# telemetry-shorter.net
KiCad netlist of a schematic drawn in EAGLE
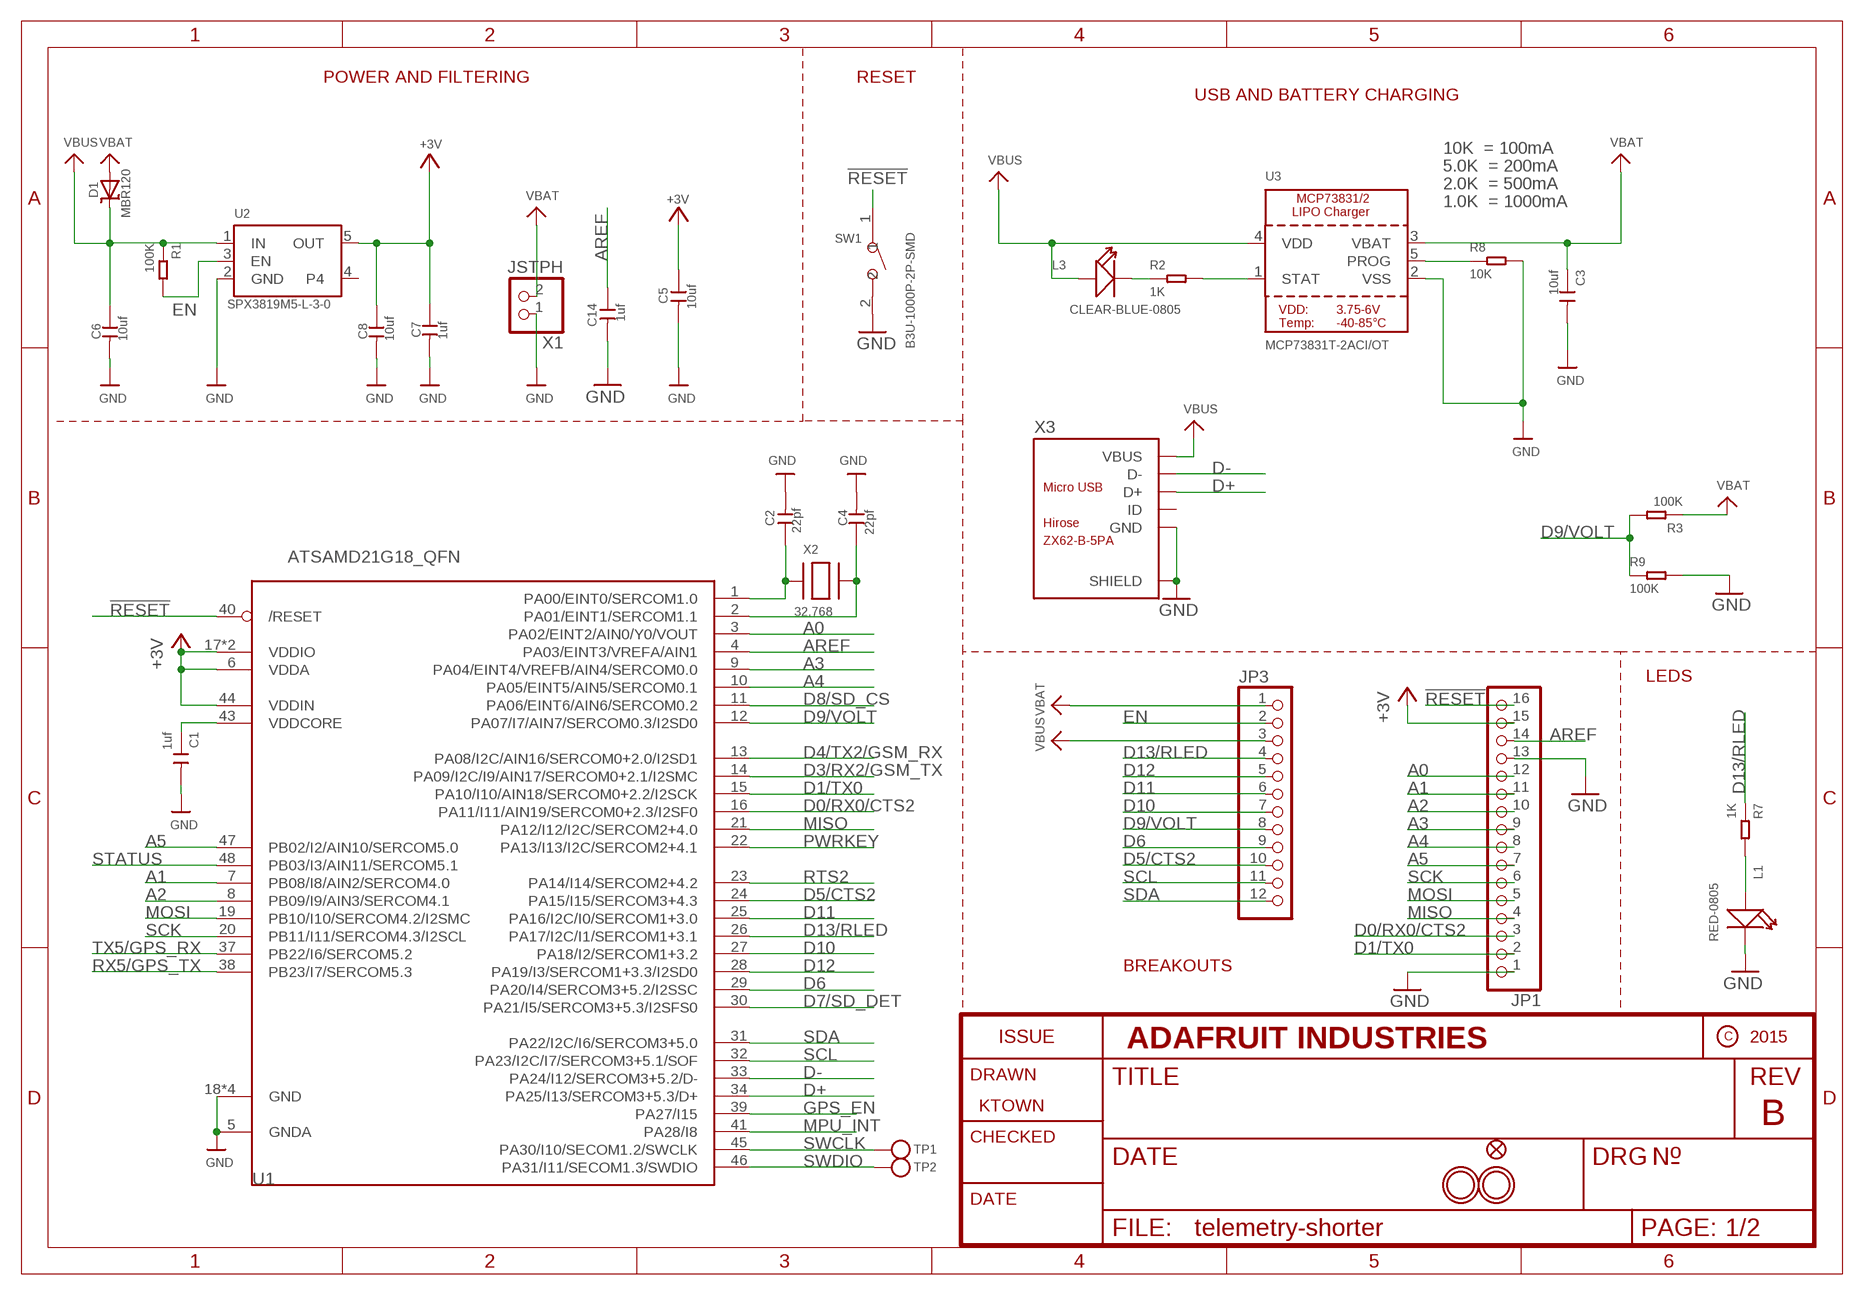
[diagram p0: schematic, sheet 1]
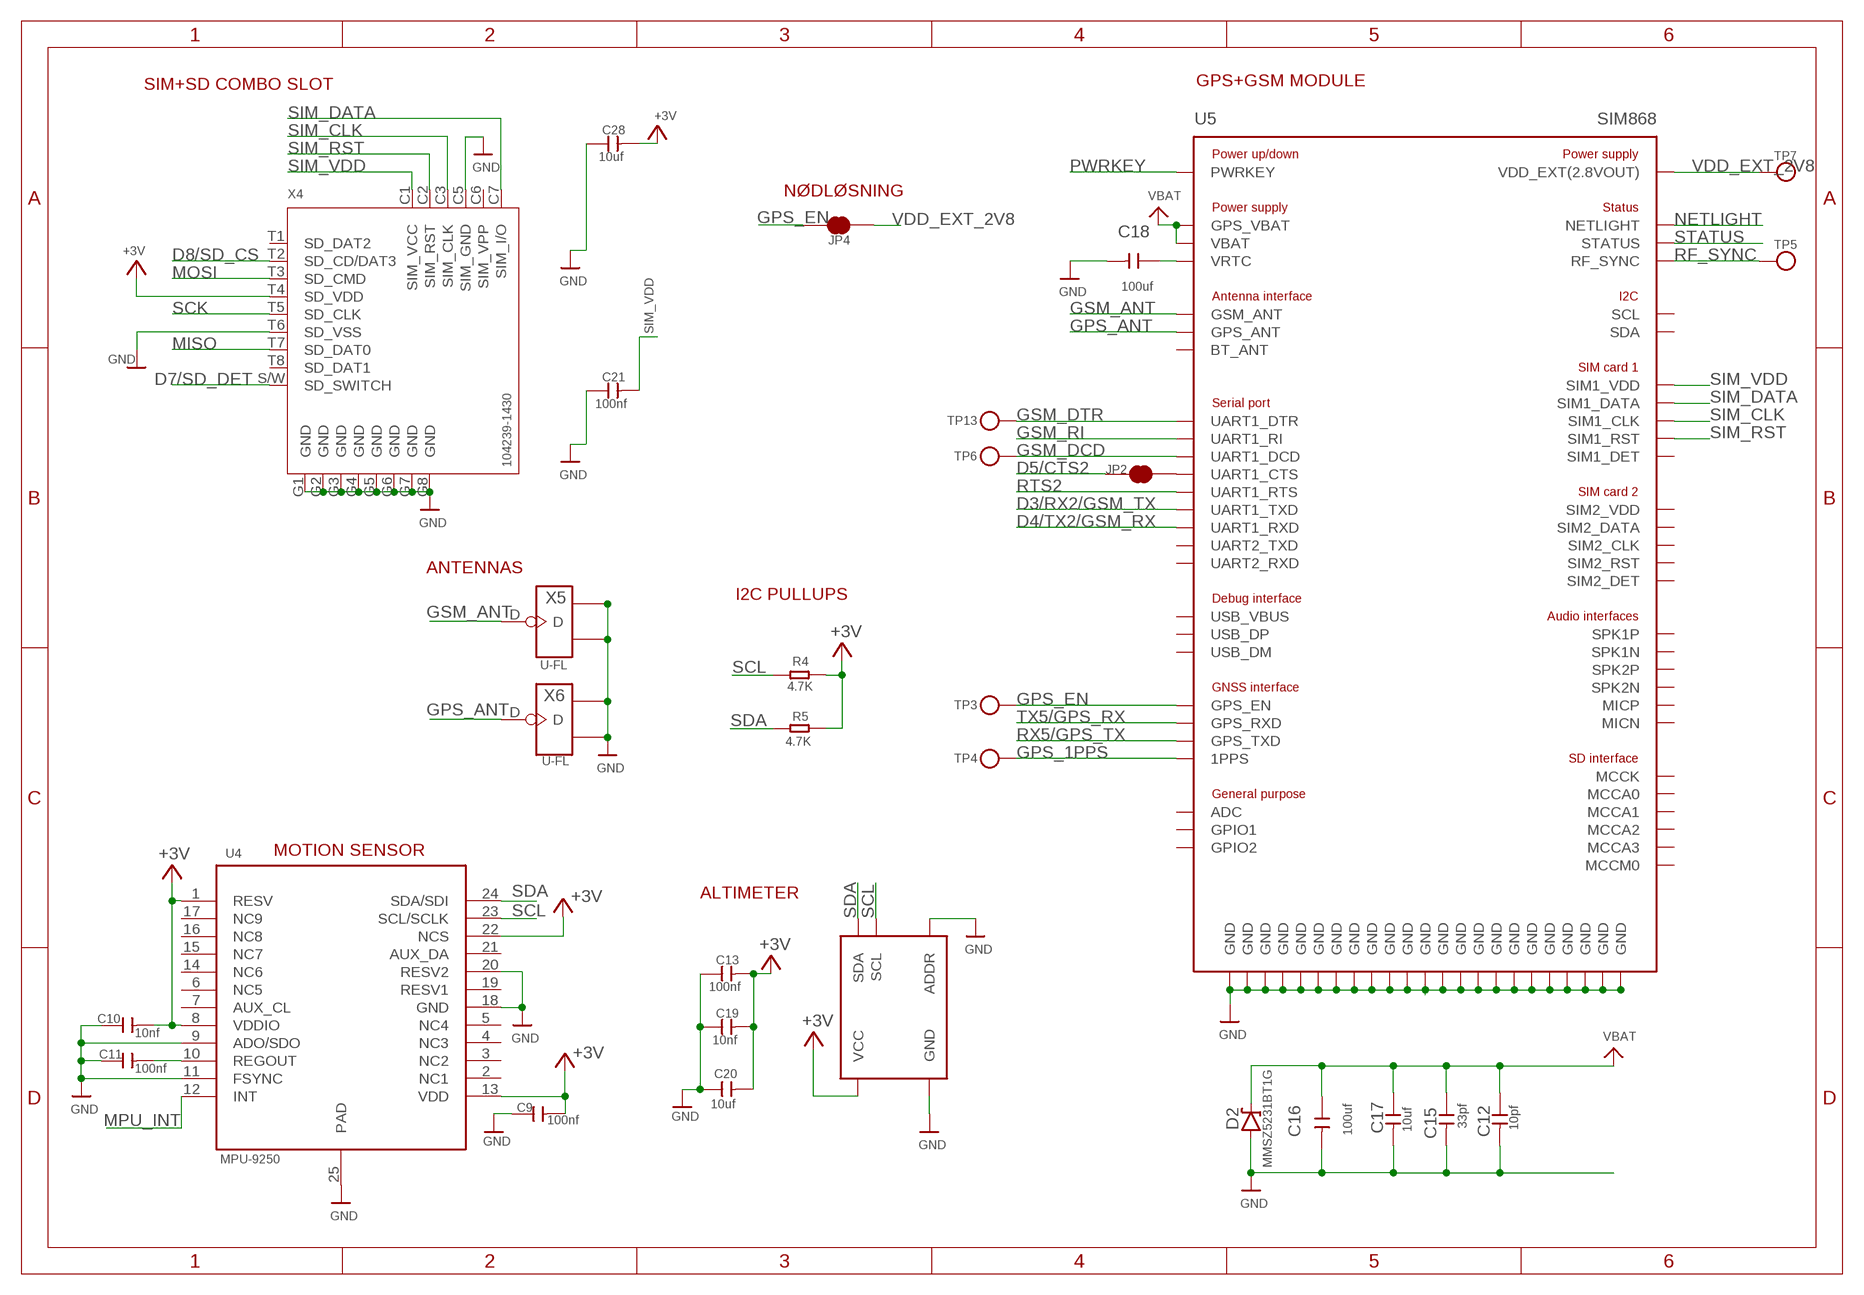
[diagram p1: schematic, sheet 2]

(export (version "E")
  (design (tool "Eeschema 10.0.6"))
  (components
    (comp (ref "C1")
      (value "1uf")
      (footprint "eagle-import:C0603")
      (fields (field (name "MPN") "CC0603KRX7R8BB105"))
      (libsource (lib "eagle-import") (part "CERAMIC-1UF-25V-10%-X7R(0603)"))
    )
    (comp (ref "C2")
      (value "22pf")
      (footprint "eagle-import:C0603")
      (fields (field (name "MPN") "CC0603JRNPO9BN220"))
      (libsource (lib "eagle-import") (part "CERAMIC-22PF-50V-5%-NPO(0603)"))
    )
    (comp (ref "C3")
      (value "10uf")
      (footprint "eagle-import:C0603")
      (fields (field (name "MPN") "CC0603KRX5R6BB106"))
      (libsource (lib "eagle-import") (part "CERAMIC-10UF-10V-10%-X5R(0603)"))
    )
    (comp (ref "C4")
      (value "22pf")
      (footprint "eagle-import:C0603")
      (fields (field (name "MPN") "CC0603JRNPO9BN220"))
      (libsource (lib "eagle-import") (part "CERAMIC-22PF-50V-5%-NPO(0603)"))
    )
    (comp (ref "C5")
      (value "10uf")
      (footprint "eagle-import:C0603")
      (fields (field (name "MPN") "CC0603KRX5R6BB106"))
      (libsource (lib "eagle-import") (part "CERAMIC-10UF-10V-10%-X5R(0603)"))
    )
    (comp (ref "C6")
      (value "10uf")
      (footprint "eagle-import:C0603")
      (fields (field (name "MPN") "CC0603KRX5R6BB106"))
      (libsource (lib "eagle-import") (part "CERAMIC-10UF-10V-10%-X5R(0603)"))
    )
    (comp (ref "C7")
      (value "1uf")
      (footprint "eagle-import:C0603")
      (fields (field (name "MPN") "CC0603KRX7R8BB105"))
      (libsource (lib "eagle-import") (part "CERAMIC-1UF-25V-10%-X7R(0603)"))
    )
    (comp (ref "C8")
      (value "10uf")
      (footprint "eagle-import:C0603")
      (fields (field (name "MPN") "CC0603KRX5R6BB106"))
      (libsource (lib "eagle-import") (part "CERAMIC-10UF-10V-10%-X5R(0603)"))
    )
    (comp (ref "C14")
      (value "1uf")
      (footprint "eagle-import:C0603")
      (fields (field (name "MPN") "CC0603KRX7R8BB105"))
      (libsource (lib "eagle-import") (part "CERAMIC-1UF-25V-10%-X7R(0603)"))
    )
    (comp (ref "D1")
      (value "MBR120")
      (footprint "eagle-import:SOD-123")
      (libsource (lib "eagle-import") (part "DIODE-SCHOTTKYSOD-123"))
    )
    (comp (ref "JP1")
      (value "HEADER-1X16ROUND")
      (footprint "eagle-import:1X16_ROUND")
      (libsource (lib "eagle-import") (part "HEADER-1X16ROUND"))
    )
    (comp (ref "JP3")
      (value "HEADER-1X12")
      (footprint "eagle-import:1X12_ROUND")
      (libsource (lib "eagle-import") (part "HEADER-1X12"))
    )
    (comp (ref "L1")
      (value "RED-0805")
      (footprint "eagle-import:LED-0805")
      (fields (field (name "MPN") "17-215SURC/S530-A2/TR8"))
      (libsource (lib "eagle-import") (part "SMD-LED-CLEAR-RED(0805)"))
    )
    (comp (ref "L3")
      (value "CLEAR-BLUE-0805")
      (footprint "eagle-import:LED-0805")
      (fields (field (name "MPN") "EL-17-215/BHC-AN1P2/3T"))
      (libsource (lib "eagle-import") (part "SMD-LED-CLEAR-BLUE(0805)"))
    )
    (comp (ref "R1")
      (value "100K")
      (footprint "eagle-import:R0603")
      (fields (field (name "MPN") "RC0603JR-07100KL"))
      (libsource (lib "eagle-import") (part "SMD-RES-100K-5%-1/10W(0603)"))
    )
    (comp (ref "R2")
      (value "1K")
      (footprint "eagle-import:R0603")
      (fields (field (name "MPN") "RC0603JR-071KL"))
      (libsource (lib "eagle-import") (part "SMD-RES-1K-5%-1/10W(0603)"))
    )
    (comp (ref "R3")
      (value "100K")
      (footprint "eagle-import:R0603")
      (fields (field (name "MPN") "RC0603FR-07100KL"))
      (libsource (lib "eagle-import") (part "SMD-RES-100K-1%-1/10W(0603)"))
    )
    (comp (ref "R7")
      (value "1K")
      (footprint "eagle-import:R0603")
      (fields (field (name "MPN") "RC0603JR-071KL"))
      (libsource (lib "eagle-import") (part "SMD-RES-1K-5%-1/10W(0603)"))
    )
    (comp (ref "R8")
      (value "10K")
      (footprint "eagle-import:R0603")
      (fields (field (name "MPN") "RC0603JR-0710KL"))
      (libsource (lib "eagle-import") (part "SMD-RES-10K-5%-1/10W(0603)"))
    )
    (comp (ref "R9")
      (value "100K")
      (footprint "eagle-import:R0603")
      (fields (field (name "MPN") "RC0603FR-07100KL"))
      (libsource (lib "eagle-import") (part "SMD-RES-100K-1%-1/10W(0603)"))
    )
    (comp (ref "SW1")
      (value "B3U-1000P-2P-SMD")
      (footprint "eagle-import:SW2-2.6-3.0X2.5X1.2+0.4MM")
      (libsource (lib "eagle-import") (part "SMD-BUTTON(2P-3.0X2.5X1.2+0.4MM)-B3U-1000P-2P-SMD"))
    )
    (comp (ref "TP1")
      (value "TESTPOINTROUND1.5MM")
      (footprint "eagle-import:TESTPOINT_ROUND_1.5MM")
      (libsource (lib "eagle-import") (part "TESTPOINTROUND1.5MM"))
    )
    (comp (ref "TP2")
      (value "TESTPOINTROUND1.5MM")
      (footprint "eagle-import:TESTPOINT_ROUND_1.5MM")
      (libsource (lib "eagle-import") (part "TESTPOINTROUND1.5MM"))
    )
    (comp (ref "U$31")
      (value "MOUNTINGHOLE2.5")
      (footprint "eagle-import:MOUNTINGHOLE_2.5_PLATED")
      (libsource (lib "eagle-import") (part "MOUNTINGHOLE2.5"))
    )
    (comp (ref "U$32")
      (value "MOUNTINGHOLE2.5")
      (footprint "eagle-import:MOUNTINGHOLE_2.5_PLATED")
      (libsource (lib "eagle-import") (part "MOUNTINGHOLE2.5"))
    )
    (comp (ref "U$34")
      (value "FIDUCIAL\"\"")
      (footprint "eagle-import:FIDUCIAL_1MM")
      (libsource (lib "eagle-import") (part "FIDUCIAL{dblquote}{dblquote}"))
    )
    (comp (ref "U1")
      (value "ATSAMD21G18_QFN")
      (footprint "eagle-import:TQFN48_7MM")
      (libsource (lib "eagle-import") (part "ATSAMD21J_QFN"))
    )
    (comp (ref "U2")
      (value "SPX3819M5-L-3-0")
      (footprint "eagle-import:SOT23-5")
      (libsource (lib "eagle-import") (part "VREG_SOT23-5"))
    )
    (comp (ref "U3")
      (value "MCP73831T-2ACI/OT")
      (footprint "eagle-import:SOT23-5")
      (libsource (lib "eagle-import") (part "MCP73831/2"))
    )
    (comp (ref "X1")
      (value "JSTPH")
      (footprint "eagle-import:JSTPH2")
      (libsource (lib "eagle-import") (part "CON_JST_PH_2PIN"))
    )
    (comp (ref "X2")
      (value "32.768")
      (footprint "eagle-import:XTAL3215")
      (libsource (lib "eagle-import") (part "XTAL-3.2X1.5"))
    )
    (comp (ref "X3")
      (value "ZX62-B-5PA")
      (footprint "eagle-import:MICRO-USB5+6P-SMD-0.65-AB")
      (fields (field (name "MFR") "Generic") (field (name "MPN") "AO1SB141B1-067"))
      (libsource (lib "eagle-import") (part "AO1SB141B1-067"))
    )
    (comp (ref "C9")
      (value "100nf")
      (footprint "eagle-import:C0603")
      (fields (field (name "MPN") "CC0603KRX7R9BB104"))
      (libsource (lib "eagle-import") (part "CERAMIC-100NF-50V-10%-X7R(0603)"))
    )
    (comp (ref "C10")
      (value "10nf")
      (footprint "eagle-import:C0603")
      (fields (field (name "MPN") "CC0603KRX7R9BB103"))
      (libsource (lib "eagle-import") (part "CERAMIC-10NF-50V-10%-X7R(0603)"))
    )
    (comp (ref "C11")
      (value "100nf")
      (footprint "eagle-import:C0603")
      (fields (field (name "MPN") "CC0603KRX7R9BB104"))
      (libsource (lib "eagle-import") (part "CERAMIC-100NF-50V-10%-X7R(0603)"))
    )
    (comp (ref "C12")
      (value "10pf")
      (footprint "eagle-import:C0603")
      (fields (field (name "MPN") "CC0603JRNPO9BN100"))
      (libsource (lib "eagle-import") (part "CERAMIC-10PF-50V-5%-NPO(0603)"))
    )
    (comp (ref "C13")
      (value "100nf")
      (footprint "eagle-import:C0603")
      (fields (field (name "MPN") "CC0603KRX7R9BB104"))
      (libsource (lib "eagle-import") (part "CERAMIC-100NF-50V-10%-X7R(0603)"))
    )
    (comp (ref "C15")
      (value "33pf")
      (footprint "eagle-import:C0603")
      (fields (field (name "MPN") "CC0603JRNPO9BN330"))
      (libsource (lib "eagle-import") (part "CERAMIC-33PF-50V-5%-NPO(0603)"))
    )
    (comp (ref "C16")
      (value "100uf")
      (footprint "eagle-import:C1206")
      (fields (field (name "MPN") "GRM31CR60J107ME39L"))
      (libsource (lib "eagle-import") (part "CERAMIC-100UF-6.3V-20%-X5R(1206)"))
    )
    (comp (ref "C17")
      (value "10uf")
      (footprint "eagle-import:C0603")
      (fields (field (name "MPN") "CC0603KRX5R6BB106"))
      (libsource (lib "eagle-import") (part "CERAMIC-10UF-10V-10%-X5R(0603)"))
    )
    (comp (ref "C18")
      (value "100uf")
      (footprint "eagle-import:C1206")
      (fields (field (name "MPN") "GRM31CR60J107ME39L"))
      (libsource (lib "eagle-import") (part "CERAMIC-100UF-6.3V-20%-X5R(1206)"))
    )
    (comp (ref "C19")
      (value "10nf")
      (footprint "eagle-import:C0603")
      (fields (field (name "MPN") "CC0603KRX7R9BB103"))
      (libsource (lib "eagle-import") (part "CERAMIC-10NF-50V-10%-X7R(0603)"))
    )
    (comp (ref "C20")
      (value "10uf")
      (footprint "eagle-import:C0603")
      (fields (field (name "MPN") "CC0603KRX5R6BB106"))
      (libsource (lib "eagle-import") (part "CERAMIC-10UF-10V-10%-X5R(0603)"))
    )
    (comp (ref "C21")
      (value "100nf")
      (footprint "eagle-import:C0603")
      (fields (field (name "MPN") "CC0603KRX7R9BB104"))
      (libsource (lib "eagle-import") (part "CERAMIC-100NF-50V-10%-X7R(0603)"))
    )
    (comp (ref "C28")
      (value "10uf")
      (footprint "eagle-import:C0603")
      (fields (field (name "MPN") "CC0603KRX5R6BB106"))
      (libsource (lib "eagle-import") (part "CERAMIC-10UF-10V-10%-X5R(0603)"))
    )
    (comp (ref "D2")
      (value "MMSZ5231BT1G")
      (footprint "eagle-import:SOD-123")
      (fields (field (name "MFR") "ON SEMICONDUCTOR"))
      (libsource (lib "eagle-import") (part "MMSZ5231BT1G"))
    )
    (comp (ref "JP2")
      (value "JUMPER-PAD-2-NC_BY_TRACE")
      (footprint "eagle-import:PAD-JUMPER-2-NC_BY_TRACE_YES_SILK")
      (libsource (lib "eagle-import") (part "JUMPER-PAD-2-NC_BY_TRACE"))
    )
    (comp (ref "JP4")
      (value "JUMPER-PAD-2-NC_BY_TRACE")
      (footprint "eagle-import:PAD-JUMPER-2-NC_BY_TRACE_YES_SILK")
      (libsource (lib "eagle-import") (part "JUMPER-PAD-2-NC_BY_TRACE"))
    )
    (comp (ref "R4")
      (value "4.7K")
      (footprint "eagle-import:R0603")
      (fields (field (name "MPN") "RC0603JR-074K7L"))
      (libsource (lib "eagle-import") (part "SMD-RES-4.7K-5%-1/10W(0603)"))
    )
    (comp (ref "R5")
      (value "4.7K")
      (footprint "eagle-import:R0603")
      (fields (field (name "MPN") "RC0603JR-074K7L"))
      (libsource (lib "eagle-import") (part "SMD-RES-4.7K-5%-1/10W(0603)"))
    )
    (comp (ref "TP3")
      (value "TESTPOINTROUND1.5MM")
      (footprint "eagle-import:TESTPOINT_ROUND_1.5MM")
      (libsource (lib "eagle-import") (part "TESTPOINTROUND1.5MM"))
    )
    (comp (ref "TP4")
      (value "TESTPOINTROUND1.5MM")
      (footprint "eagle-import:TESTPOINT_ROUND_1.5MM")
      (libsource (lib "eagle-import") (part "TESTPOINTROUND1.5MM"))
    )
    (comp (ref "TP5")
      (value "TESTPOINTROUND1.5MM")
      (footprint "eagle-import:TESTPOINT_ROUND_1.5MM")
      (libsource (lib "eagle-import") (part "TESTPOINTROUND1.5MM"))
    )
    (comp (ref "TP6")
      (value "TESTPOINTROUND1.5MM")
      (footprint "eagle-import:TESTPOINT_ROUND_1.5MM")
      (libsource (lib "eagle-import") (part "TESTPOINTROUND1.5MM"))
    )
    (comp (ref "TP7")
      (value "TESTPOINTROUND1.5MM")
      (footprint "eagle-import:TESTPOINT_ROUND_1.5MM")
      (libsource (lib "eagle-import") (part "TESTPOINTROUND1.5MM"))
    )
    (comp (ref "TP13")
      (value "TESTPOINTROUND1.5MM")
      (footprint "eagle-import:TESTPOINT_ROUND_1.5MM")
      (libsource (lib "eagle-import") (part "TESTPOINTROUND1.5MM"))
    )
    (comp (ref "U4")
      (value "MPU-9250")
      (footprint "eagle-import:LEAD-QFN24")
      (libsource (lib "eagle-import") (part "MPU-9250"))
    )
    (comp (ref "U5")
      (value "SIM868")
      (footprint "eagle-import:SIM868")
      (libsource (lib "eagle-import") (part "SIM868"))
    )
    (comp (ref "U6")
      (value "BMP280")
      (footprint "eagle-import:LGA-8")
      (libsource (lib "eagle-import") (part "BMP280"))
    )
    (comp (ref "X4")
      (value "104239-1430")
      (footprint "eagle-import:MOLEX-SD+SIM-104239")
      (fields (field (name "MPN") "VSHO-21-3301"))
      (libsource (lib "eagle-import") (part "MOLEX-SD+SIM-104239"))
    )
    (comp (ref "X5")
      (value "U-FL")
      (footprint "eagle-import:U-FL3P-SMD-2.6X2.6X1.0MM")
      (libsource (lib "eagle-import") (part "ANTENNA-CONN-U-FL(3P)"))
    )
    (comp (ref "X6")
      (value "U-FL")
      (footprint "eagle-import:U-FL3P-SMD-2.6X2.6X1.0MM")
      (libsource (lib "eagle-import") (part "ANTENNA-CONN-U-FL(3P)"))
    )
  )
  (nets
    (net (code "1") (name "+3V") (class "Default")
      (node (ref "C10") (pin "2") (pinfunction "2_2") (pintype "passive"))
      (node (ref "C13") (pin "2") (pinfunction "2_2") (pintype "passive"))
      (node (ref "C19") (pin "2") (pinfunction "2_2") (pintype "passive"))
      (node (ref "C20") (pin "2") (pinfunction "2_2") (pintype "passive"))
      (node (ref "C28") (pin "2") (pinfunction "2_2") (pintype "passive"))
      (node (ref "C5") (pin "1") (pinfunction "1_1") (pintype "passive"))
      (node (ref "C7") (pin "1") (pinfunction "1_1") (pintype "passive"))
      (node (ref "C8") (pin "1") (pinfunction "1_1") (pintype "passive"))
      (node (ref "C9") (pin "2") (pinfunction "2_2") (pintype "passive"))
      (node (ref "JP1") (pin "15") (pinfunction "15_15") (pintype "passive"))
      (node (ref "R4") (pin "2") (pinfunction "2_2") (pintype "passive"))
      (node (ref "R5") (pin "2") (pinfunction "2_2") (pintype "passive"))
      (node (ref "U1") (pin "17") (pinfunction "VDDIO_17") (pintype "power_in"))
      (node (ref "U1") (pin "36") (pinfunction "VDDIO_36") (pintype "power_in"))
      (node (ref "U1") (pin "44") (pinfunction "VDDIN_44") (pintype "power_in"))
      (node (ref "U1") (pin "6") (pinfunction "VDDA_6") (pintype "power_in"))
      (node (ref "U2") (pin "5") (pinfunction "OUT_5") (pintype "power_in"))
      (node (ref "U4") (pin "1") (pinfunction "RESV_1") (pintype "bidirectional"))
      (node (ref "U4") (pin "13") (pinfunction "VDD_13") (pintype "bidirectional"))
      (node (ref "U4") (pin "22") (pinfunction "NCS_22") (pintype "bidirectional"))
      (node (ref "U4") (pin "8") (pinfunction "VDDIO_8") (pintype "bidirectional"))
      (node (ref "U6") (pin "P2") (pinfunction "VCC_P2") (pintype "bidirectional"))
      (node (ref "U6") (pin "P6") (pinfunction "VCC_P6") (pintype "bidirectional"))
      (node (ref "U6") (pin "P8") (pinfunction "VCC_P8") (pintype "bidirectional"))
      (node (ref "X4") (pin "T4") (pinfunction "SD_VDD_T4") (pintype "bidirectional"))
    )
    (net (code "2") (name "A0") (class "Default")
      (node (ref "JP1") (pin "12") (pinfunction "12_12") (pintype "passive"))
      (node (ref "U1") (pin "3") (pinfunction "PA02/EINT2/AIN0/Y0/VOUT_3") (pintype "bidirectional"))
    )
    (net (code "3") (name "A1") (class "Default")
      (node (ref "JP1") (pin "11") (pinfunction "11_11") (pintype "passive"))
      (node (ref "U1") (pin "7") (pinfunction "PB08/I8/AIN2/SERCOM4.0_7") (pintype "bidirectional"))
    )
    (net (code "4") (name "A2") (class "Default")
      (node (ref "JP1") (pin "10") (pinfunction "10_10") (pintype "passive"))
      (node (ref "U1") (pin "8") (pinfunction "PB09/I9/AIN3/SERCOM4.1_8") (pintype "bidirectional"))
    )
    (net (code "5") (name "A3") (class "Default")
      (node (ref "JP1") (pin "9") (pinfunction "9_9") (pintype "passive"))
      (node (ref "U1") (pin "9") (pinfunction "PA04/EINT4/VREFB/AIN4/SERCOM0.0_9") (pintype "bidirectional"))
    )
    (net (code "6") (name "A4") (class "Default")
      (node (ref "JP1") (pin "8") (pinfunction "8_8") (pintype "passive"))
      (node (ref "U1") (pin "10") (pinfunction "PA05/EINT5/AIN5/SERCOM0.1_10") (pintype "bidirectional"))
    )
    (net (code "7") (name "A5") (class "Default")
      (node (ref "JP1") (pin "7") (pinfunction "7_7") (pintype "passive"))
      (node (ref "U1") (pin "47") (pinfunction "PB02/I2/AIN10/SERCOM5.0_47") (pintype "bidirectional"))
    )
    (net (code "8") (name "AREF") (class "Default")
      (node (ref "C14") (pin "1") (pinfunction "1_1") (pintype "passive"))
      (node (ref "JP1") (pin "14") (pinfunction "14_14") (pintype "passive"))
      (node (ref "U1") (pin "4") (pinfunction "PA03/EINT3/VREFA/AIN1_4") (pintype "bidirectional"))
    )
    (net (code "9") (name "D+") (class "Default")
      (node (ref "U1") (pin "34") (pinfunction "PA25/I13/SERCOM3+5.3/D+_34") (pintype "bidirectional"))
      (node (ref "X3") (pin "3") (pinfunction "D+_3") (pintype "bidirectional"))
    )
    (net (code "10") (name "D-") (class "Default")
      (node (ref "U1") (pin "33") (pinfunction "PA24/I12/SERCOM3+5.2/D-_33") (pintype "bidirectional"))
      (node (ref "X3") (pin "2") (pinfunction "D-_2") (pintype "bidirectional"))
    )
    (net (code "11") (name "D0{slash}RX0{slash}CTS2") (class "Default")
      (node (ref "JP1") (pin "3") (pinfunction "3_3") (pintype "passive"))
      (node (ref "U1") (pin "16") (pinfunction "PA11/I11/AIN19/SERCOM0+2.3/I2SF0_16") (pintype "bidirectional"))
    )
    (net (code "12") (name "D1{slash}TX0") (class "Default")
      (node (ref "JP1") (pin "2") (pinfunction "2_2") (pintype "passive"))
      (node (ref "U1") (pin "15") (pinfunction "PA10/I10/AIN18/SERCOM0+2.2/I2SCK_15") (pintype "bidirectional"))
    )
    (net (code "13") (name "D3{slash}RX2{slash}GSM_TX") (class "Default")
      (node (ref "U1") (pin "14") (pinfunction "PA09/I2C/I9/AIN17/SERCOM0+2.1/I2SMC_14") (pintype "bidirectional"))
      (node (ref "U5") (pin "1_") (pinfunction "UART1_TXD_1_") (pintype "output"))
    )
    (net (code "14") (name "D4{slash}TX2{slash}GSM_RX") (class "Default")
      (node (ref "U1") (pin "13") (pinfunction "PA08/I2C/AIN16/SERCOM0+2.0/I2SD1_13") (pintype "bidirectional"))
      (node (ref "U5") (pin "2_") (pinfunction "UART1_RXD_2_") (pintype "input"))
    )
    (net (code "15") (name "D5{slash}CTS2") (class "Default")
      (node (ref "JP2") (pin "1") (pinfunction "1_1") (pintype "passive"))
      (node (ref "JP3") (pin "10") (pinfunction "10_10") (pintype "passive"))
      (node (ref "U1") (pin "24") (pinfunction "PA15/I15/SERCOM3+4.3_24") (pintype "bidirectional"))
    )
    (net (code "16") (name "D6") (class "Default")
      (node (ref "JP3") (pin "9") (pinfunction "9_9") (pintype "passive"))
      (node (ref "U1") (pin "29") (pinfunction "PA20/I4/SERCOM3+5.2/I2SSC_29") (pintype "bidirectional"))
    )
    (net (code "17") (name "D7{slash}SD_DET") (class "Default")
      (node (ref "U1") (pin "30") (pinfunction "PA21/I5/SERCOM3+5.3/I2SFS0_30") (pintype "bidirectional"))
      (node (ref "X4") (pin "S/W") (pinfunction "SD_SWITCH_S/W") (pintype "bidirectional"))
    )
    (net (code "18") (name "D8{slash}SD_CS") (class "Default")
      (node (ref "U1") (pin "11") (pinfunction "PA06/EINT6/AIN6/SERCOM0.2_11") (pintype "bidirectional"))
      (node (ref "X4") (pin "T2") (pinfunction "SD_CD/DAT3_T2") (pintype "bidirectional"))
    )
    (net (code "19") (name "D9{slash}VOLT") (class "Default")
      (node (ref "JP3") (pin "8") (pinfunction "8_8") (pintype "passive"))
      (node (ref "R3") (pin "2") (pinfunction "2_2") (pintype "passive"))
      (node (ref "R9") (pin "1") (pinfunction "1_1") (pintype "passive"))
      (node (ref "U1") (pin "12") (pinfunction "PA07/I7/AIN7/SERCOM0.3/I2SD0_12") (pintype "bidirectional"))
    )
    (net (code "20") (name "D10") (class "Default")
      (node (ref "JP3") (pin "7") (pinfunction "7_7") (pintype "passive"))
      (node (ref "U1") (pin "27") (pinfunction "PA18/I2/SERCOM1+3.2_27") (pintype "bidirectional"))
    )
    (net (code "21") (name "D11") (class "Default")
      (node (ref "JP3") (pin "6") (pinfunction "6_6") (pintype "passive"))
      (node (ref "U1") (pin "25") (pinfunction "PA16/I2C/I0/SERCOM1+3.0_25") (pintype "bidirectional"))
    )
    (net (code "22") (name "D12") (class "Default")
      (node (ref "JP3") (pin "5") (pinfunction "5_5") (pintype "passive"))
      (node (ref "U1") (pin "28") (pinfunction "PA19/I3/SERCOM1+3.3/I2SD0_28") (pintype "bidirectional"))
    )
    (net (code "23") (name "D13{slash}RLED") (class "Default")
      (node (ref "JP3") (pin "4") (pinfunction "4_4") (pintype "passive"))
      (node (ref "R7") (pin "1") (pinfunction "1_1") (pintype "passive"))
      (node (ref "U1") (pin "26") (pinfunction "PA17/I2C/I1/SERCOM1+3.1_26") (pintype "bidirectional"))
    )
    (net (code "24") (name "EN") (class "Default")
      (node (ref "JP3") (pin "2") (pinfunction "2_2") (pintype "passive"))
      (node (ref "R1") (pin "2") (pinfunction "2_2") (pintype "passive"))
      (node (ref "U2") (pin "3") (pinfunction "EN_3") (pintype "input"))
    )
    (net (code "25") (name "GND") (class "Default")
      (node (ref "C1") (pin "2") (pinfunction "2_2") (pintype "passive"))
      (node (ref "C10") (pin "1") (pinfunction "1_1") (pintype "passive"))
      (node (ref "C11") (pin "1") (pinfunction "1_1") (pintype "passive"))
      (node (ref "C12") (pin "2") (pinfunction "2_2") (pintype "passive"))
      (node (ref "C13") (pin "1") (pinfunction "1_1") (pintype "passive"))
      (node (ref "C14") (pin "2") (pinfunction "2_2") (pintype "passive"))
      (node (ref "C15") (pin "2") (pinfunction "2_2") (pintype "passive"))
      (node (ref "C16") (pin "2") (pinfunction "2_2") (pintype "passive"))
      (node (ref "C17") (pin "2") (pinfunction "2_2") (pintype "passive"))
      (node (ref "C18") (pin "2") (pinfunction "2_2") (pintype "passive"))
      (node (ref "C19") (pin "1") (pinfunction "1_1") (pintype "passive"))
      (node (ref "C2") (pin "2") (pinfunction "2_2") (pintype "passive"))
      (node (ref "C20") (pin "1") (pinfunction "1_1") (pintype "passive"))
      (node (ref "C21") (pin "1") (pinfunction "1_1") (pintype "passive"))
      (node (ref "C28") (pin "1") (pinfunction "1_1") (pintype "passive"))
      (node (ref "C3") (pin "2") (pinfunction "2_2") (pintype "passive"))
      (node (ref "C4") (pin "2") (pinfunction "2_2") (pintype "passive"))
      (node (ref "C5") (pin "2") (pinfunction "2_2") (pintype "passive"))
      (node (ref "C6") (pin "2") (pinfunction "2_2") (pintype "passive"))
      (node (ref "C7") (pin "2") (pinfunction "2_2") (pintype "passive"))
      (node (ref "C8") (pin "2") (pinfunction "2_2") (pintype "passive"))
      (node (ref "C9") (pin "1") (pinfunction "1_1") (pintype "passive"))
      (node (ref "D2") (pin "A") (pinfunction "A_A") (pintype "passive"))
      (node (ref "JP1") (pin "1") (pinfunction "1_1") (pintype "passive"))
      (node (ref "JP1") (pin "13") (pinfunction "13_13") (pintype "passive"))
      (node (ref "L1") (pin "-") (pinfunction "-_-") (pintype "passive"))
      (node (ref "R8") (pin "2") (pinfunction "2_2") (pintype "passive"))
      (node (ref "R9") (pin "2") (pinfunction "2_2") (pintype "passive"))
      (node (ref "SW1") (pin "2") (pinfunction "2_2") (pintype "bidirectional"))
      (node (ref "U1") (pin "18") (pinfunction "GND_18") (pintype "power_in"))
      (node (ref "U1") (pin "35") (pinfunction "GND_35") (pintype "power_in"))
      (node (ref "U1") (pin "42") (pinfunction "GND_42") (pintype "power_in"))
      (node (ref "U1") (pin "5") (pinfunction "GNDA_5") (pintype "power_in"))
      (node (ref "U1") (pin "THERMAL") (pinfunction "GND_THERMAL") (pintype "power_in"))
      (node (ref "U2") (pin "2") (pinfunction "GND_2") (pintype "power_in"))
      (node (ref "U3") (pin "2") (pinfunction "VSS_2") (pintype "power_in"))
      (node (ref "U4") (pin "11") (pinfunction "FSYNC_11") (pintype "bidirectional"))
      (node (ref "U4") (pin "18") (pinfunction "GND_18") (pintype "bidirectional"))
      (node (ref "U4") (pin "20") (pinfunction "RESV2_20") (pintype "bidirectional"))
      (node (ref "U4") (pin "25") (pinfunction "PAD_25") (pintype "bidirectional"))
      (node (ref "U4") (pin "9") (pinfunction "ADO/SDO_9") (pintype "bidirectional"))
      (node (ref "U5") (pin "13_") (pinfunction "GND_13_") (pintype "power_in"))
      (node (ref "U5") (pin "19_") (pinfunction "GND_19_") (pintype "power_in"))
      (node (ref "U5") (pin "21_") (pinfunction "GND_21_") (pintype "power_in"))
      (node (ref "U5") (pin "27_") (pinfunction "GND_27_") (pintype "power_in"))
      (node (ref "U5") (pin "30_") (pinfunction "GND_30_") (pintype "power_in"))
      (node (ref "U5") (pin "31_") (pinfunction "GND_31_") (pintype "power_in"))
      (node (ref "U5") (pin "33_") (pinfunction "GND_33_") (pintype "power_in"))
      (node (ref "U5") (pin "36_") (pinfunction "GND_36_") (pintype "power_in"))
      (node (ref "U5") (pin "37_") (pinfunction "GND_37_") (pintype "power_in"))
      (node (ref "U5") (pin "45_") (pinfunction "GND_45_") (pintype "power_in"))
      (node (ref "U5") (pin "63_") (pinfunction "GND_63_") (pintype "power_in"))
      (node (ref "U5") (pin "66_") (pinfunction "GND_66_") (pintype "power_in"))
      (node (ref "U5") (pin "67_") (pinfunction "GND_67_") (pintype "power_in"))
      (node (ref "U5") (pin "69_") (pinfunction "GND_69_") (pintype "power_in"))
      (node (ref "U5") (pin "70_") (pinfunction "GND_70_") (pintype "power_in"))
      (node (ref "U5") (pin "71_") (pinfunction "GND_71_") (pintype "power_in"))
      (node (ref "U5") (pin "72_") (pinfunction "GND_72_") (pintype "power_in"))
      (node (ref "U5") (pin "73_") (pinfunction "GND_73_") (pintype "power_in"))
      (node (ref "U5") (pin "74_") (pinfunction "GND_74_") (pintype "power_in"))
      (node (ref "U5") (pin "75_") (pinfunction "GND_75_") (pintype "power_in"))
      (node (ref "U5") (pin "76_") (pinfunction "GND_76_") (pintype "power_in"))
      (node (ref "U5") (pin "77_") (pinfunction "GND_77_") (pintype "power_in"))
      (node (ref "U5") (pin "8_") (pinfunction "GND_8_") (pintype "power_in"))
      (node (ref "U6") (pin "P1") (pinfunction "GND_P1") (pintype "bidirectional"))
      (node (ref "U6") (pin "P5") (pinfunction "ADDR_P5") (pintype "bidirectional"))
      (node (ref "U6") (pin "P7") (pinfunction "GND_P7") (pintype "bidirectional"))
      (node (ref "X1") (pin "1") (pinfunction "1_1") (pintype "passive"))
      (node (ref "X3") (pin "5") (pinfunction "GND_5") (pintype "power_in"))
      (node (ref "X3") (pin "P1") (pinfunction "SHIELD_P1") (pintype "power_in"))
      (node (ref "X3") (pin "P2") (pinfunction "SHIELD_P2") (pintype "power_in"))
      (node (ref "X3") (pin "P3") (pinfunction "SHIELD_P3") (pintype "power_in"))
      (node (ref "X3") (pin "P4") (pinfunction "SHIELD_P4") (pintype "power_in"))
      (node (ref "X3") (pin "P5") (pinfunction "SHIELD_P5") (pintype "power_in"))
      (node (ref "X3") (pin "P6") (pinfunction "SHIELD_P6") (pintype "power_in"))
      (node (ref "X4") (pin "C5") (pinfunction "SIM_GND_C5") (pintype "bidirectional"))
      (node (ref "X4") (pin "G1") (pinfunction "GND_G1") (pintype "power_in"))
      (node (ref "X4") (pin "G2") (pinfunction "GND_G2") (pintype "power_in"))
      (node (ref "X4") (pin "G3") (pinfunction "GND_G3") (pintype "power_in"))
      (node (ref "X4") (pin "G4") (pinfunction "GND_G4") (pintype "power_in"))
      (node (ref "X4") (pin "G5") (pinfunction "GND_G5") (pintype "power_in"))
      (node (ref "X4") (pin "G6") (pinfunction "GND_G6") (pintype "power_in"))
      (node (ref "X4") (pin "G7") (pinfunction "GND_G7") (pintype "power_in"))
      (node (ref "X4") (pin "G8") (pinfunction "GND_G8") (pintype "power_in"))
      (node (ref "X4") (pin "T6") (pinfunction "SD_VSS_T6") (pintype "bidirectional"))
      (node (ref "X5") (pin "GND1") (pinfunction "GND1_GND1") (pintype "bidirectional"))
      (node (ref "X5") (pin "GND2") (pinfunction "GND2_GND2") (pintype "bidirectional"))
      (node (ref "X6") (pin "GND1") (pinfunction "GND1_GND1") (pintype "bidirectional"))
      (node (ref "X6") (pin "GND2") (pinfunction "GND2_GND2") (pintype "bidirectional"))
    )
    (net (code "26") (name "GPS_1PPS") (class "Default")
      (node (ref "TP4") (pin "P$1") (pinfunction "P$1_P$1") (pintype "bidirectional"))
      (node (ref "U5") (pin "60_") (pinfunction "1PPS_60_") (pintype "input"))
    )
    (net (code "27") (name "GPS_ANT") (class "Default")
      (node (ref "U5") (pin "68_") (pinfunction "GPS_ANT_68_") (pintype "bidirectional"))
      (node (ref "X6") (pin "D") (pinfunction "D_D") (pintype "bidirectional"))
    )
    (net (code "28") (name "GPS_EN") (class "Default")
      (node (ref "JP4") (pin "1") (pinfunction "1_1") (pintype "passive"))
      (node (ref "TP3") (pin "P$1") (pinfunction "P$1_P$1") (pintype "bidirectional"))
      (node (ref "U1") (pin "39") (pinfunction "PA27/I15_39") (pintype "bidirectional"))
      (node (ref "U5") (pin "59_") (pinfunction "GPS_EN_59_") (pintype "input"))
    )
    (net (code "29") (name "GSM_ANT") (class "Default")
      (node (ref "U5") (pin "32_") (pinfunction "GSM_ANT_32_") (pintype "input"))
      (node (ref "X5") (pin "D") (pinfunction "D_D") (pintype "bidirectional"))
    )
    (net (code "30") (name "GSM_DCD") (class "Default")
      (node (ref "TP6") (pin "P$1") (pinfunction "P$1_P$1") (pintype "bidirectional"))
      (node (ref "U5") (pin "5_") (pinfunction "UART1_DCD_5_") (pintype "output"))
    )
    (net (code "31") (name "GSM_DTR") (class "Default")
      (node (ref "TP13") (pin "P$1") (pinfunction "P$1_P$1") (pintype "bidirectional"))
      (node (ref "U5") (pin "6_") (pinfunction "UART1_DTR_6_") (pintype "input"))
    )
    (net (code "32") (name "GSM_RI") (class "Default")
      (node (ref "U5") (pin "7_") (pinfunction "UART1_RI_7_") (pintype "output"))
    )
    (net (code "33") (name "MISO") (class "Default")
      (node (ref "JP1") (pin "4") (pinfunction "4_4") (pintype "passive"))
      (node (ref "U1") (pin "21") (pinfunction "PA12/I12/I2C/SERCOM2+4.0_21") (pintype "bidirectional"))
      (node (ref "X4") (pin "T7") (pinfunction "SD_DAT0_T7") (pintype "bidirectional"))
    )
    (net (code "34") (name "MOSI") (class "Default")
      (node (ref "JP1") (pin "5") (pinfunction "5_5") (pintype "passive"))
      (node (ref "U1") (pin "19") (pinfunction "PB10/I10/SERCOM4.2/I2SMC_19") (pintype "bidirectional"))
      (node (ref "X4") (pin "T3") (pinfunction "SD_CMD_T3") (pintype "bidirectional"))
    )
    (net (code "35") (name "MPU_INT") (class "Default")
      (node (ref "U1") (pin "41") (pinfunction "PA28/I8_41") (pintype "bidirectional"))
      (node (ref "U4") (pin "12") (pinfunction "INT_12") (pintype "bidirectional"))
    )
    (net (code "36") (name "NETLIGHT") (class "Default")
      (node (ref "U5") (pin "41_") (pinfunction "NETLIGHT_41_") (pintype "output"))
    )
    (net (code "37") (name "Net-(L1-Pad+)") (class "Default")
      (node (ref "L1") (pin "+") (pinfunction "+_+") (pintype "passive"))
      (node (ref "R7") (pin "2") (pinfunction "2_2") (pintype "passive"))
    )
    (net (code "38") (name "Net-(L3-Pad-)") (class "Default")
      (node (ref "L3") (pin "-") (pinfunction "-_-") (pintype "passive"))
      (node (ref "R2") (pin "1") (pinfunction "1_1") (pintype "passive"))
    )
    (net (code "39") (name "Net-(U1-PA00{slash}EINT0{slash}SERCOM1.0)") (class "Default")
      (node (ref "C2") (pin "1") (pinfunction "1_1") (pintype "passive"))
      (node (ref "U1") (pin "1") (pinfunction "PA00/EINT0/SERCOM1.0_1") (pintype "bidirectional"))
      (node (ref "X2") (pin "P$1") (pinfunction "P$1_P$1") (pintype "bidirectional"))
    )
    (net (code "40") (name "Net-(U1-PA01{slash}EINT1{slash}SERCOM1.1)") (class "Default")
      (node (ref "C4") (pin "1") (pinfunction "1_1") (pintype "passive"))
      (node (ref "U1") (pin "2") (pinfunction "PA01/EINT1/SERCOM1.1_2") (pintype "bidirectional"))
      (node (ref "X2") (pin "P$2") (pinfunction "P$2_P$2") (pintype "bidirectional"))
    )
    (net (code "41") (name "Net-(U1-VDDCORE)") (class "Default")
      (node (ref "C1") (pin "1") (pinfunction "1_1") (pintype "passive"))
      (node (ref "U1") (pin "43") (pinfunction "VDDCORE_43") (pintype "power_in"))
    )
    (net (code "42") (name "Net-(U3-PROG)") (class "Default")
      (node (ref "R8") (pin "1") (pinfunction "1_1") (pintype "passive"))
      (node (ref "U3") (pin "5") (pinfunction "PROG_5") (pintype "input"))
    )
    (net (code "43") (name "Net-(U3-STAT)") (class "Default")
      (node (ref "R2") (pin "2") (pinfunction "2_2") (pintype "passive"))
      (node (ref "U3") (pin "1") (pinfunction "STAT_1") (pintype "output"))
    )
    (net (code "44") (name "Net-(U4-REGOUT)") (class "Default")
      (node (ref "C11") (pin "2") (pinfunction "2_2") (pintype "passive"))
      (node (ref "U4") (pin "10") (pinfunction "REGOUT_10") (pintype "bidirectional"))
    )
    (net (code "45") (name "Net-(U5-UART1_CTS)") (class "Default")
      (node (ref "JP2") (pin "2") (pinfunction "2_2") (pintype "passive"))
      (node (ref "U5") (pin "4_") (pinfunction "UART1_CTS_4_") (pintype "output"))
    )
    (net (code "46") (name "Net-(U5-VRTC)") (class "Default")
      (node (ref "C18") (pin "1") (pinfunction "1_1") (pintype "passive"))
      (node (ref "U5") (pin "28_") (pinfunction "VRTC_28_") (pintype "power_in"))
    )
    (net (code "47") (name "PWRKEY") (class "Default")
      (node (ref "U1") (pin "22") (pinfunction "PA13/I13/I2C/SERCOM2+4.1_22") (pintype "bidirectional"))
      (node (ref "U5") (pin "39_") (pinfunction "PWRKEY_39_") (pintype "input"))
    )
    (net (code "48") (name "RF_SYNC") (class "Default")
      (node (ref "TP5") (pin "P$1") (pinfunction "P$1_P$1") (pintype "bidirectional"))
      (node (ref "U5") (pin "29_") (pinfunction "RF_SYNC_29_") (pintype "output"))
    )
    (net (code "49") (name "RTS2") (class "Default")
      (node (ref "U1") (pin "23") (pinfunction "PA14/I14/SERCOM2+4.2_23") (pintype "bidirectional"))
      (node (ref "U5") (pin "3_") (pinfunction "UART1_RTS_3_") (pintype "input"))
    )
    (net (code "50") (name "RX5{slash}GPS_TX") (class "Default")
      (node (ref "U1") (pin "38") (pinfunction "PB23/I7/SERCOM5.3_38") (pintype "bidirectional"))
      (node (ref "U5") (pin "61_") (pinfunction "GPS_TXD_61_") (pintype "output"))
    )
    (net (code "51") (name "SCK") (class "Default")
      (node (ref "JP1") (pin "6") (pinfunction "6_6") (pintype "passive"))
      (node (ref "U1") (pin "20") (pinfunction "PB11/I11/SERCOM4.3/I2SCL_20") (pintype "bidirectional"))
      (node (ref "X4") (pin "T5") (pinfunction "SD_CLK_T5") (pintype "bidirectional"))
    )
    (net (code "52") (name "SCL") (class "Default")
      (node (ref "JP3") (pin "11") (pinfunction "11_11") (pintype "passive"))
      (node (ref "R4") (pin "1") (pinfunction "1_1") (pintype "passive"))
      (node (ref "U1") (pin "32") (pinfunction "PA23/I2C/I7/SERCOM3+5.1/SOF_32") (pintype "bidirectional"))
      (node (ref "U4") (pin "23") (pinfunction "SCL/SCLK_23") (pintype "bidirectional"))
      (node (ref "U6") (pin "P4") (pinfunction "SCL_P4") (pintype "bidirectional"))
    )
    (net (code "53") (name "SDA") (class "Default")
      (node (ref "JP3") (pin "12") (pinfunction "12_12") (pintype "passive"))
      (node (ref "R5") (pin "1") (pinfunction "1_1") (pintype "passive"))
      (node (ref "U1") (pin "31") (pinfunction "PA22/I2C/I6/SERCOM3+5.0_31") (pintype "bidirectional"))
      (node (ref "U4") (pin "24") (pinfunction "SDA/SDI_24") (pintype "bidirectional"))
      (node (ref "U6") (pin "P3") (pinfunction "SDA_P3") (pintype "bidirectional"))
    )
    (net (code "54") (name "SIM2_VDD") (class "Default")
      (node (ref "U5") (pin "56_") (pinfunction "SIM2_VDD_56_") (pintype "power_in"))
    )
    (net (code "55") (name "SIM_CLK") (class "Default")
      (node (ref "U5") (pin "16_") (pinfunction "SIM1_CLK_16_") (pintype "output"))
      (node (ref "X4") (pin "C3") (pinfunction "SIM_CLK_C3") (pintype "bidirectional"))
    )
    (net (code "56") (name "SIM_DATA") (class "Default")
      (node (ref "U5") (pin "15_") (pinfunction "SIM1_DATA_15_") (pintype "bidirectional"))
      (node (ref "X4") (pin "C7") (pinfunction "SIM_I/O_C7") (pintype "bidirectional"))
    )
    (net (code "57") (name "SIM_RST") (class "Default")
      (node (ref "U5") (pin "17_") (pinfunction "SIM1_RST_17_") (pintype "output"))
      (node (ref "X4") (pin "C2") (pinfunction "SIM_RST_C2") (pintype "bidirectional"))
    )
    (net (code "58") (name "SIM_VDD") (class "Default")
      (node (ref "C21") (pin "2") (pinfunction "2_2") (pintype "passive"))
      (node (ref "U5") (pin "18_") (pinfunction "SIM1_VDD_18_") (pintype "power_in"))
      (node (ref "X4") (pin "C1") (pinfunction "SIM_VCC_C1") (pintype "bidirectional"))
    )
    (net (code "59") (name "STATUS") (class "Default")
      (node (ref "U1") (pin "48") (pinfunction "PB03/I3/AIN11/SERCOM5.1_48") (pintype "bidirectional"))
      (node (ref "U5") (pin "42_") (pinfunction "STATUS_42_") (pintype "output"))
    )
    (net (code "60") (name "SWCLK") (class "Default")
      (node (ref "TP1") (pin "P$1") (pinfunction "P$1_P$1") (pintype "bidirectional"))
      (node (ref "U1") (pin "45") (pinfunction "PA30/I10/SECOM1.2/SWCLK_45") (pintype "bidirectional"))
    )
    (net (code "61") (name "SWDIO") (class "Default")
      (node (ref "TP2") (pin "P$1") (pinfunction "P$1_P$1") (pintype "bidirectional"))
      (node (ref "U1") (pin "46") (pinfunction "PA31/I11/SECOM1.3/SWDIO_46") (pintype "bidirectional"))
    )
    (net (code "62") (name "TX5{slash}GPS_RX") (class "Default")
      (node (ref "U1") (pin "37") (pinfunction "PB22/I6/SERCOM5.2_37") (pintype "bidirectional"))
      (node (ref "U5") (pin "62_") (pinfunction "GPS_RXD_62_") (pintype "input"))
    )
    (net (code "63") (name "USB_VBUS") (class "Default")
      (node (ref "U5") (pin "24_") (pinfunction "USB_VBUS_24_") (pintype "power_in"))
    )
    (net (code "64") (name "VBAT") (class "Default")
      (node (ref "C12") (pin "1") (pinfunction "1_1") (pintype "passive"))
      (node (ref "C15") (pin "1") (pinfunction "1_1") (pintype "passive"))
      (node (ref "C16") (pin "1") (pinfunction "1_1") (pintype "passive"))
      (node (ref "C17") (pin "1") (pinfunction "1_1") (pintype "passive"))
      (node (ref "C3") (pin "1") (pinfunction "1_1") (pintype "passive"))
      (node (ref "D1") (pin "A") (pinfunction "A_A") (pintype "passive"))
      (node (ref "D2") (pin "C") (pinfunction "C_C") (pintype "passive"))
      (node (ref "JP3") (pin "1") (pinfunction "1_1") (pintype "passive"))
      (node (ref "R3") (pin "1") (pinfunction "1_1") (pintype "passive"))
      (node (ref "U3") (pin "3") (pinfunction "VBAT_3") (pintype "power_in"))
      (node (ref "U5") (pin "34_") (pinfunction "GPS_VBAT_34_") (pintype "power_in"))
      (node (ref "U5") (pin "35_") (pinfunction "VBAT_35_") (pintype "power_in"))
      (node (ref "X1") (pin "2") (pinfunction "2_2") (pintype "passive"))
    )
    (net (code "65") (name "VBUS") (class "Default")
      (node (ref "C6") (pin "1") (pinfunction "1_1") (pintype "passive"))
      (node (ref "D1") (pin "C") (pinfunction "C_C") (pintype "passive"))
      (node (ref "JP3") (pin "3") (pinfunction "3_3") (pintype "passive"))
      (node (ref "L3") (pin "+") (pinfunction "+_+") (pintype "passive"))
      (node (ref "R1") (pin "1") (pinfunction "1_1") (pintype "passive"))
      (node (ref "U2") (pin "1") (pinfunction "IN_1") (pintype "power_in"))
      (node (ref "U3") (pin "4") (pinfunction "VDD_4") (pintype "power_in"))
      (node (ref "X3") (pin "1") (pinfunction "VBUS_1") (pintype "power_in"))
    )
    (net (code "66") (name "VDD_EXT_2V8") (class "Default")
      (node (ref "JP4") (pin "2") (pinfunction "2_2") (pintype "passive"))
      (node (ref "TP7") (pin "P$1") (pinfunction "P$1_P$1") (pintype "bidirectional"))
      (node (ref "U5") (pin "40_") (pinfunction "VDD_EXT(2.8VOUT)_40_") (pintype "power_in"))
    )
    (net (code "67") (name "unconnected-(U2-P4-Pad4)") (class "Default")
      (node (ref "U2") (pin "4") (pinfunction "P4_4") (pintype "bidirectional"))
    )
    (net (code "68") (name "unconnected-(U4-AUX_CL-Pad7)") (class "Default")
      (node (ref "U4") (pin "7") (pinfunction "AUX_CL_7") (pintype "bidirectional"))
    )
    (net (code "69") (name "unconnected-(U4-AUX_DA-Pad21)") (class "Default")
      (node (ref "U4") (pin "21") (pinfunction "AUX_DA_21") (pintype "bidirectional"))
    )
    (net (code "70") (name "unconnected-(U4-NC1-Pad2)") (class "Default")
      (node (ref "U4") (pin "2") (pinfunction "NC1_2") (pintype "bidirectional"))
    )
    (net (code "71") (name "unconnected-(U4-NC2-Pad3)") (class "Default")
      (node (ref "U4") (pin "3") (pinfunction "NC2_3") (pintype "bidirectional"))
    )
    (net (code "72") (name "unconnected-(U4-NC3-Pad4)") (class "Default")
      (node (ref "U4") (pin "4") (pinfunction "NC3_4") (pintype "bidirectional"))
    )
    (net (code "73") (name "unconnected-(U4-NC4-Pad5)") (class "Default")
      (node (ref "U4") (pin "5") (pinfunction "NC4_5") (pintype "bidirectional"))
    )
    (net (code "74") (name "unconnected-(U4-NC5-Pad6)") (class "Default")
      (node (ref "U4") (pin "6") (pinfunction "NC5_6") (pintype "bidirectional"))
    )
    (net (code "75") (name "unconnected-(U4-NC6-Pad14)") (class "Default")
      (node (ref "U4") (pin "14") (pinfunction "NC6_14") (pintype "bidirectional"))
    )
    (net (code "76") (name "unconnected-(U4-NC7-Pad15)") (class "Default")
      (node (ref "U4") (pin "15") (pinfunction "NC7_15") (pintype "bidirectional"))
    )
    (net (code "77") (name "unconnected-(U4-NC8-Pad16)") (class "Default")
      (node (ref "U4") (pin "16") (pinfunction "NC8_16") (pintype "bidirectional"))
    )
    (net (code "78") (name "unconnected-(U4-NC9-Pad17)") (class "Default")
      (node (ref "U4") (pin "17") (pinfunction "NC9_17") (pintype "bidirectional"))
    )
    (net (code "79") (name "unconnected-(U4-RESV1-Pad19)") (class "Default")
      (node (ref "U4") (pin "19") (pinfunction "RESV1_19") (pintype "bidirectional"))
    )
    (net (code "80") (name "unconnected-(U5-ADC-Pad38_)") (class "Default")
      (node (ref "U5") (pin "38_") (pinfunction "ADC_38_") (pintype "input"))
    )
    (net (code "81") (name "unconnected-(U5-BT_ANT-Pad20_)") (class "Default")
      (node (ref "U5") (pin "20_") (pinfunction "BT_ANT_20_") (pintype "bidirectional"))
    )
    (net (code "82") (name "unconnected-(U5-GPIO1-Pad57_)") (class "Default")
      (node (ref "U5") (pin "57_") (pinfunction "GPIO1_57_") (pintype "bidirectional"))
    )
    (net (code "83") (name "unconnected-(U5-GPIO2-Pad58_)") (class "Default")
      (node (ref "U5") (pin "58_") (pinfunction "GPIO2_58_") (pintype "bidirectional"))
    )
    (net (code "84") (name "unconnected-(U5-MCCA0-Pad49_)") (class "Default")
      (node (ref "U5") (pin "49_") (pinfunction "MCCA0_49_") (pintype "bidirectional"))
    )
    (net (code "85") (name "unconnected-(U5-MCCA1-Pad48_)") (class "Default")
      (node (ref "U5") (pin "48_") (pinfunction "MCCA1_48_") (pintype "bidirectional"))
    )
    (net (code "86") (name "unconnected-(U5-MCCA2-Pad47_)") (class "Default")
      (node (ref "U5") (pin "47_") (pinfunction "MCCA2_47_") (pintype "bidirectional"))
    )
    (net (code "87") (name "unconnected-(U5-MCCA3-Pad46_)") (class "Default")
      (node (ref "U5") (pin "46_") (pinfunction "MCCA3_46_") (pintype "bidirectional"))
    )
    (net (code "88") (name "unconnected-(U5-MCCK-Pad50_)") (class "Default")
      (node (ref "U5") (pin "50_") (pinfunction "MCCK_50_") (pintype "bidirectional"))
    )
    (net (code "89") (name "unconnected-(U5-MCCM0-Pad51_)") (class "Default")
      (node (ref "U5") (pin "51_") (pinfunction "MCCM0_51_") (pintype "bidirectional"))
    )
    (net (code "90") (name "unconnected-(U5-MICN-Pad10_)") (class "Default")
      (node (ref "U5") (pin "10_") (pinfunction "MICN_10_") (pintype "input"))
    )
    (net (code "91") (name "unconnected-(U5-MICP-Pad9_)") (class "Default")
      (node (ref "U5") (pin "9_") (pinfunction "MICP_9_") (pintype "input"))
    )
    (net (code "92") (name "unconnected-(U5-SCL-Pad65_)") (class "Default")
      (node (ref "U5") (pin "65_") (pinfunction "SCL_65_") (pintype "output"))
    )
    (net (code "93") (name "unconnected-(U5-SDA-Pad64_)") (class "Default")
      (node (ref "U5") (pin "64_") (pinfunction "SDA_64_") (pintype "bidirectional"))
    )
    (net (code "94") (name "unconnected-(U5-SIM1_DET-Pad14_)") (class "Default")
      (node (ref "U5") (pin "14_") (pinfunction "SIM1_DET_14_") (pintype "input"))
    )
    (net (code "95") (name "unconnected-(U5-SIM2_CLK-Pad54_)") (class "Default")
      (node (ref "U5") (pin "54_") (pinfunction "SIM2_CLK_54_") (pintype "output"))
    )
    (net (code "96") (name "unconnected-(U5-SIM2_DATA-Pad53_)") (class "Default")
      (node (ref "U5") (pin "53_") (pinfunction "SIM2_DATA_53_") (pintype "bidirectional"))
    )
    (net (code "97") (name "unconnected-(U5-SIM2_DET-Pad52_)") (class "Default")
      (node (ref "U5") (pin "52_") (pinfunction "SIM2_DET_52_") (pintype "input"))
    )
    (net (code "98") (name "unconnected-(U5-SIM2_RST-Pad55_)") (class "Default")
      (node (ref "U5") (pin "55_") (pinfunction "SIM2_RST_55_") (pintype "output"))
    )
    (net (code "99") (name "unconnected-(U5-SPK1N-Pad12_)") (class "Default")
      (node (ref "U5") (pin "12_") (pinfunction "SPK1N_12_") (pintype "output"))
    )
    (net (code "100") (name "unconnected-(U5-SPK1P-Pad11_)") (class "Default")
      (node (ref "U5") (pin "11_") (pinfunction "SPK1P_11_") (pintype "output"))
    )
    (net (code "101") (name "unconnected-(U5-SPK2N-Pad43_)") (class "Default")
      (node (ref "U5") (pin "43_") (pinfunction "SPK2N_43_") (pintype "output"))
    )
    (net (code "102") (name "unconnected-(U5-SPK2P-Pad44_)") (class "Default")
      (node (ref "U5") (pin "44_") (pinfunction "SPK2P_44_") (pintype "output"))
    )
    (net (code "103") (name "unconnected-(U5-UART2_RXD-Pad23_)") (class "Default")
      (node (ref "U5") (pin "23_") (pinfunction "UART2_RXD_23_") (pintype "input"))
    )
    (net (code "104") (name "unconnected-(U5-UART2_TXD-Pad22_)") (class "Default")
      (node (ref "U5") (pin "22_") (pinfunction "UART2_TXD_22_") (pintype "output"))
    )
    (net (code "105") (name "unconnected-(U5-USB_DM-Pad26_)") (class "Default")
      (node (ref "U5") (pin "26_") (pinfunction "USB_DM_26_") (pintype "bidirectional"))
    )
    (net (code "106") (name "unconnected-(U5-USB_DP-Pad25_)") (class "Default")
      (node (ref "U5") (pin "25_") (pinfunction "USB_DP_25_") (pintype "bidirectional"))
    )
    (net (code "107") (name "unconnected-(X3-ID-Pad4)") (class "Default")
      (node (ref "X3") (pin "4") (pinfunction "ID_4") (pintype "bidirectional"))
    )
    (net (code "108") (name "unconnected-(X4-SD_DAT1-PadT8)") (class "Default")
      (node (ref "X4") (pin "T8") (pinfunction "SD_DAT1_T8") (pintype "bidirectional"))
    )
    (net (code "109") (name "unconnected-(X4-SD_DAT2-PadT1)") (class "Default")
      (node (ref "X4") (pin "T1") (pinfunction "SD_DAT2_T1") (pintype "bidirectional"))
    )
    (net (code "110") (name "unconnected-(X4-SIM_VPP-PadC6)") (class "Default")
      (node (ref "X4") (pin "C6") (pinfunction "SIM_VPP_C6") (pintype "bidirectional"))
    )
    (net (code "111") (name "~{RESET}") (class "Default")
      (node (ref "JP1") (pin "16") (pinfunction "16_16") (pintype "passive"))
      (node (ref "SW1") (pin "1") (pinfunction "1_1") (pintype "bidirectional"))
      (node (ref "U1") (pin "40") (pinfunction "/RESET_40") (pintype "bidirectional"))
    )
  )
)
